# XBee_FX_I2C_Interface_v1_4.net
KiCad netlist of a schematic drawn in EAGLE
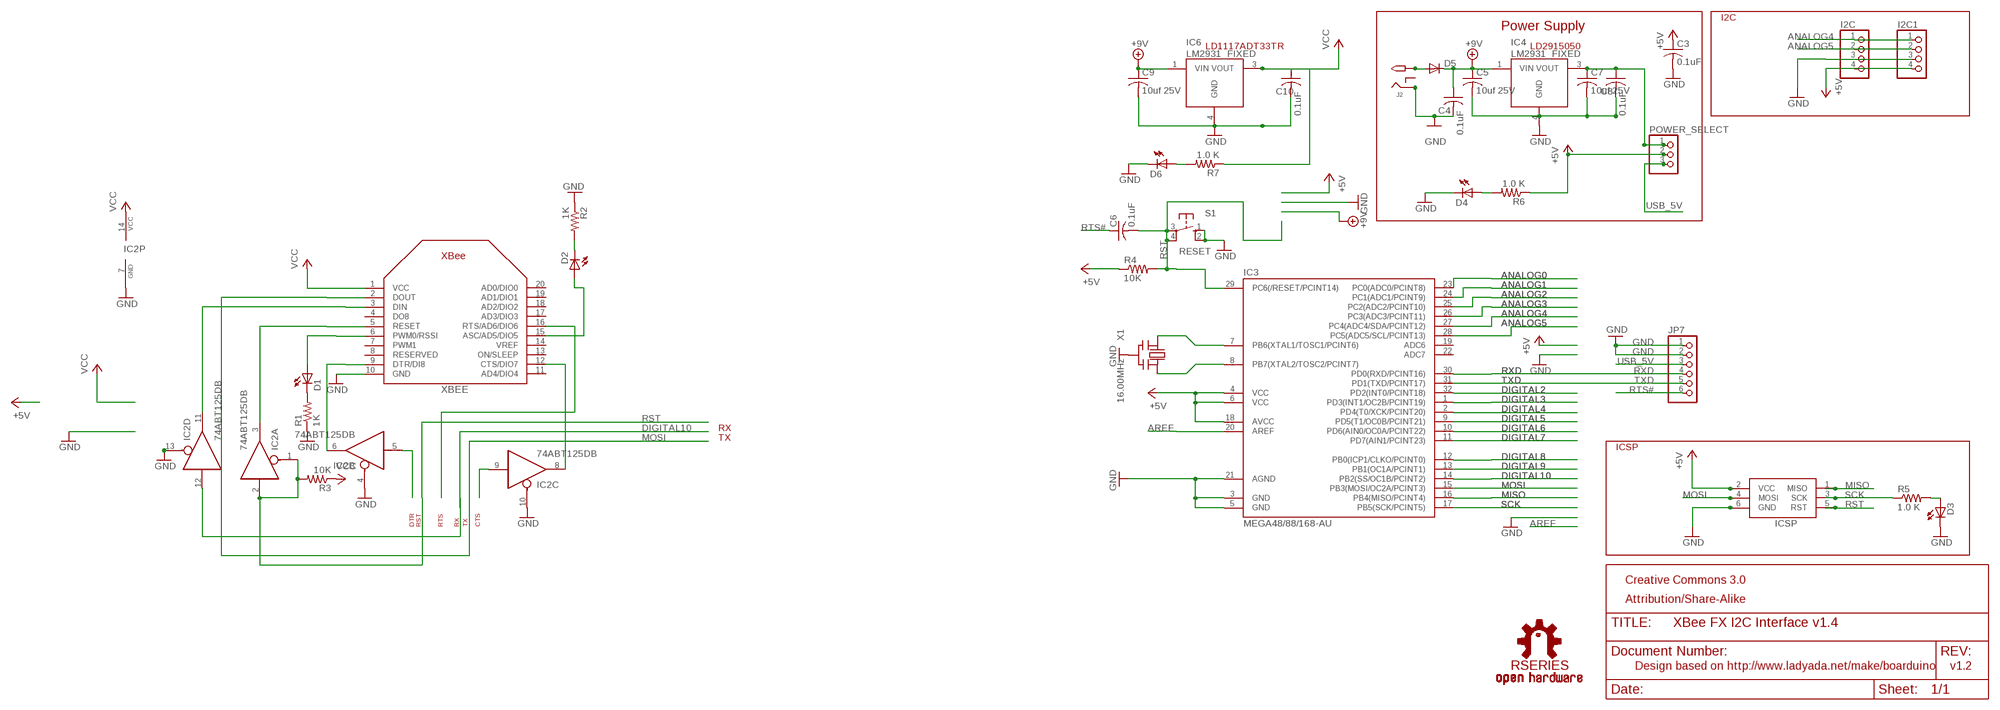
[diagram p0: schematic, sheet 1]

(export (version "E")
  (design (tool "Eeschema 10.0.6"))
  (components
    (comp (ref "C3")
      (value "0.1uF")
      (footprint "eagle-import:C1206K")
      (libsource (lib "eagle-import") (part "C-USC1206K"))
    )
    (comp (ref "C4")
      (value "0.1uF")
      (footprint "eagle-import:C1206K")
      (libsource (lib "eagle-import") (part "C-USC1206K"))
    )
    (comp (ref "C5")
      (value "10uf 25V")
      (footprint "eagle-import:C1206K")
      (libsource (lib "eagle-import") (part "rcl_C-USC1206K"))
    )
    (comp (ref "C6")
      (value "0.1uF")
      (footprint "eagle-import:C1206K")
      (libsource (lib "eagle-import") (part "C-USC1206K"))
    )
    (comp (ref "C7")
      (value "10uf 25V")
      (footprint "eagle-import:C1206K")
      (libsource (lib "eagle-import") (part "rcl_C-USC1206K"))
    )
    (comp (ref "C8")
      (value "0.1uF")
      (footprint "eagle-import:C1206K")
      (libsource (lib "eagle-import") (part "C-USC1206K"))
    )
    (comp (ref "C9")
      (value "10uf 25V")
      (footprint "eagle-import:C1206K")
      (libsource (lib "eagle-import") (part "rcl_C-USC1206K"))
    )
    (comp (ref "C10")
      (value "0.1uF")
      (footprint "eagle-import:C1206K")
      (libsource (lib "eagle-import") (part "C-USC1206K"))
    )
    (comp (ref "D1")
      (value "LEDCHIPLED_1206")
      (footprint "eagle-import:CHIPLED_1206")
      (libsource (lib "eagle-import") (part "LEDCHIPLED_1206"))
    )
    (comp (ref "D2")
      (value "LEDCHIPLED_1206")
      (footprint "eagle-import:CHIPLED_1206")
      (libsource (lib "eagle-import") (part "LEDCHIPLED_1206"))
    )
    (comp (ref "D3")
      (value "RED")
      (footprint "eagle-import:CHIPLED_1206")
      (libsource (lib "eagle-import") (part "LEDCHIPLED_1206"))
    )
    (comp (ref "D4")
      (value "LEDCHIPLED_1206")
      (footprint "eagle-import:CHIPLED_1206")
      (libsource (lib "eagle-import") (part "LEDCHIPLED_1206"))
    )
    (comp (ref "D5")
      (value "DIODE-SMB")
      (footprint "eagle-import:SMB")
      (libsource (lib "eagle-import") (part "DIODE-SMB"))
    )
    (comp (ref "D6")
      (value "LEDCHIPLED_1206")
      (footprint "eagle-import:CHIPLED_1206")
      (libsource (lib "eagle-import") (part "LEDCHIPLED_1206"))
    )
    (comp (ref "I2C")
      (value "PINHD-1X4CB")
      (footprint "eagle-import:1X04-CB")
      (libsource (lib "eagle-import") (part "PINHD-1X4CB"))
    )
    (comp (ref "I2C1")
      (value "PINHD-1X4CB")
      (footprint "eagle-import:1X04-CB")
      (libsource (lib "eagle-import") (part "PINHD-1X4CB"))
    )
    (comp (ref "IC2")
      (value "74ABT125DB")
      (footprint "eagle-import:SSOP14")
      (libsource (lib "eagle-import") (part "74125DBABT"))
    )
    (comp (ref "IC3")
      (value "MEGA48/88/168-AU")
      (footprint "eagle-import:TQFP32-08")
      (libsource (lib "eagle-import") (part "MEGA48/88/168-AU"))
    )
    (comp (ref "IC4")
      (value "LM2931_FIXED")
      (footprint "eagle-import:DPAK")
      (libsource (lib "eagle-import") (part "LM2931_FIXED"))
    )
    (comp (ref "IC6")
      (value "LM2931_FIXED")
      (footprint "eagle-import:DPAK")
      (libsource (lib "eagle-import") (part "LM2931_FIXED"))
    )
    (comp (ref "ICSP")
      (value "AVRISP-6")
      (footprint "eagle-import:AVRISP")
      (libsource (lib "eagle-import") (part "AVRISP-6"))
    )
    (comp (ref "J2")
      (value "2.1MMJACK")
      (footprint "eagle-import:PJ-102A")
      (libsource (lib "eagle-import") (part "2.1MMJACK"))
    )
    (comp (ref "JP7")
      (value "PINHD-1X6CLEAN")
      (footprint "eagle-import:1X06-CLEAN")
      (libsource (lib "eagle-import") (part "PINHD-1X6CLEAN"))
    )
    (comp (ref "POWER_SELECT")
      (value "PINHD-1X3")
      (footprint "eagle-import:1X03")
      (libsource (lib "eagle-import") (part "PINHD-1X3"))
    )
    (comp (ref "R1")
      (value "1K")
      (footprint "eagle-import:R1206")
      (libsource (lib "eagle-import") (part "rcl-ez_R-US_R1206"))
    )
    (comp (ref "R2")
      (value "1K")
      (footprint "eagle-import:R1206")
      (libsource (lib "eagle-import") (part "rcl-ez_R-US_R1206"))
    )
    (comp (ref "R3")
      (value "10K")
      (footprint "eagle-import:R1206")
      (libsource (lib "eagle-import") (part "rcl-ez_R-US_R1206"))
    )
    (comp (ref "R4")
      (value "10K")
      (footprint "eagle-import:R1206")
      (libsource (lib "eagle-import") (part "rcl-ez_R-US_R1206"))
    )
    (comp (ref "R5")
      (value "1.0 K")
      (footprint "eagle-import:M1206")
      (libsource (lib "eagle-import") (part "R-US_M1206"))
    )
    (comp (ref "R6")
      (value "1.0 K")
      (footprint "eagle-import:M1206")
      (libsource (lib "eagle-import") (part "R-US_M1206"))
    )
    (comp (ref "R7")
      (value "1.0 K")
      (footprint "eagle-import:M1206")
      (libsource (lib "eagle-import") (part "R-US_M1206"))
    )
    (comp (ref "S1")
      (value "RESET")
      (footprint "eagle-import:B3F-10XX")
      (libsource (lib "eagle-import") (part "10-XX"))
    )
    (comp (ref "U$6")
      (value "RSERIES-OSHW-LOGOMEDIUM")
      (footprint "eagle-import:RSERIES-OSHW-LOGO-MEDIUM")
      (libsource (lib "eagle-import") (part "RSERIES-OSHW-LOGOMEDIUM"))
    )
    (comp (ref "X1")
      (value "16.00MHz")
      (footprint "eagle-import:CERM_OSC")
      (libsource (lib "eagle-import") (part "CERMOSCILL"))
    )
    (comp (ref "XBEE")
      (value "XBEE")
      (footprint "eagle-import:XBEE")
      (libsource (lib "eagle-import") (part "XBEE"))
    )
  )
  (nets
    (net (code "1") (name "+5V") (class "Default")
      (node (ref "C3") (pin "1") (pinfunction "1_1") (pintype "passive"))
      (node (ref "I2C") (pin "4") (pinfunction "4_4") (pintype "passive"))
      (node (ref "I2C1") (pin "4") (pinfunction "4_4") (pintype "passive"))
      (node (ref "IC3") (pin "18") (pinfunction "AVCC_18") (pintype "passive"))
      (node (ref "IC3") (pin "4") (pinfunction "VCC_4") (pintype "power_in"))
      (node (ref "IC3") (pin "6") (pinfunction "VCC_6") (pintype "power_in"))
      (node (ref "ICSP") (pin "2") (pinfunction "VCC_2") (pintype "power_in"))
      (node (ref "POWER_SELECT") (pin "2") (pinfunction "2_2") (pintype "passive"))
      (node (ref "R4") (pin "1") (pinfunction "1_1") (pintype "passive"))
      (node (ref "R6") (pin "1") (pinfunction "1_1") (pintype "passive"))
    )
    (net (code "2") (name "+9V") (class "Default")
      (node (ref "C4") (pin "1") (pinfunction "1_1") (pintype "passive"))
      (node (ref "C5") (pin "1") (pinfunction "1_1") (pintype "passive"))
      (node (ref "C9") (pin "1") (pinfunction "1_1") (pintype "passive"))
      (node (ref "D5") (pin "C") (pinfunction "C_C") (pintype "passive"))
      (node (ref "IC4") (pin "1") (pinfunction "VIN_1") (pintype "bidirectional"))
      (node (ref "IC6") (pin "1") (pinfunction "VIN_1") (pintype "bidirectional"))
    )
    (net (code "3") (name "/ANALOG0") (class "Default")
      (node (ref "IC3") (pin "23") (pinfunction "PC0(ADC0/PCINT8)_23") (pintype "bidirectional"))
    )
    (net (code "4") (name "/ANALOG1") (class "Default")
      (node (ref "IC3") (pin "24") (pinfunction "PC1(ADC1/PCINT9)_24") (pintype "bidirectional"))
    )
    (net (code "5") (name "/ANALOG2") (class "Default")
      (node (ref "IC3") (pin "25") (pinfunction "PC2(ADC2/PCINT10)_25") (pintype "bidirectional"))
    )
    (net (code "6") (name "/ANALOG3") (class "Default")
      (node (ref "IC3") (pin "26") (pinfunction "PC3(ADC3/PCINT11)_26") (pintype "bidirectional"))
    )
    (net (code "7") (name "/ANALOG4") (class "Default")
      (node (ref "I2C") (pin "1") (pinfunction "1_1") (pintype "passive"))
      (node (ref "I2C1") (pin "1") (pinfunction "1_1") (pintype "passive"))
      (node (ref "IC3") (pin "27") (pinfunction "PC4(ADC4/SDA/PCINT12)_27") (pintype "bidirectional"))
    )
    (net (code "8") (name "/ANALOG5") (class "Default")
      (node (ref "I2C") (pin "2") (pinfunction "2_2") (pintype "passive"))
      (node (ref "I2C1") (pin "2") (pinfunction "2_2") (pintype "passive"))
      (node (ref "IC3") (pin "28") (pinfunction "PC5(ADC5/SCL/PCINT13)_28") (pintype "bidirectional"))
    )
    (net (code "9") (name "/AREF") (class "Default")
      (node (ref "IC3") (pin "20") (pinfunction "AREF_20") (pintype "passive"))
    )
    (net (code "10") (name "/DIGITAL2") (class "Default")
      (node (ref "IC3") (pin "32") (pinfunction "PD2(INT0/PCINT18)_32") (pintype "bidirectional"))
    )
    (net (code "11") (name "/DIGITAL3") (class "Default")
      (node (ref "IC3") (pin "1") (pinfunction "PD3(INT1/OC2B/PCINT19)_1") (pintype "bidirectional"))
    )
    (net (code "12") (name "/DIGITAL4") (class "Default")
      (node (ref "IC3") (pin "2") (pinfunction "PD4(T0/XCK/PCINT20)_2") (pintype "bidirectional"))
    )
    (net (code "13") (name "/DIGITAL5") (class "Default")
      (node (ref "IC3") (pin "9") (pinfunction "PD5(T1/OC0B/PCINT21)_9") (pintype "bidirectional"))
    )
    (net (code "14") (name "/DIGITAL6") (class "Default")
      (node (ref "IC3") (pin "10") (pinfunction "PD6(AIN0/OC0A/PCINT22)_10") (pintype "bidirectional"))
    )
    (net (code "15") (name "/DIGITAL7") (class "Default")
      (node (ref "IC3") (pin "11") (pinfunction "PD7(AIN1/PCINT23)_11") (pintype "bidirectional"))
    )
    (net (code "16") (name "/DIGITAL8") (class "Default")
      (node (ref "IC3") (pin "12") (pinfunction "PB0(ICP1/CLKO/PCINT0)_12") (pintype "bidirectional"))
    )
    (net (code "17") (name "/DIGITAL9") (class "Default")
      (node (ref "IC3") (pin "13") (pinfunction "PB1(OC1A/PCINT1)_13") (pintype "bidirectional"))
    )
    (net (code "18") (name "/DIGITAL10") (class "Default")
      (node (ref "IC2") (pin "12") (pinfunction "I_12") (pintype "input"))
      (node (ref "IC3") (pin "14") (pinfunction "PB2(SS/OC1B/PCINT2)_14") (pintype "bidirectional"))
    )
    (net (code "19") (name "/MISO") (class "Default")
      (node (ref "IC3") (pin "16") (pinfunction "PB4(MISO/PCINT4)_16") (pintype "bidirectional"))
      (node (ref "ICSP") (pin "1") (pinfunction "MISO_1") (pintype "input"))
    )
    (net (code "20") (name "/MOSI") (class "Default")
      (node (ref "IC3") (pin "15") (pinfunction "PB3(MOSI/OC2A/PCINT3)_15") (pintype "bidirectional"))
      (node (ref "ICSP") (pin "4") (pinfunction "MOSI_4") (pintype "output"))
      (node (ref "XBEE") (pin "2") (pinfunction "DOUT_2") (pintype "output"))
    )
    (net (code "21") (name "/RST") (class "Default")
      (node (ref "C6") (pin "2") (pinfunction "2_2") (pintype "passive"))
      (node (ref "IC2") (pin "1") (pinfunction "OE_1") (pintype "input"))
      (node (ref "IC2") (pin "2") (pinfunction "I_2") (pintype "input"))
      (node (ref "IC3") (pin "29") (pinfunction "PC6(/RESET/PCINT14)_29") (pintype "bidirectional"))
      (node (ref "ICSP") (pin "5") (pinfunction "RST_5") (pintype "output"))
      (node (ref "R3") (pin "2") (pinfunction "2_2") (pintype "passive"))
      (node (ref "R4") (pin "2") (pinfunction "2_2") (pintype "passive"))
      (node (ref "S1") (pin "3") (pinfunction "P_3") (pintype "passive"))
      (node (ref "S1") (pin "4") (pinfunction "P1_4") (pintype "passive"))
    )
    (net (code "22") (name "/RTS#") (class "Default")
      (node (ref "C6") (pin "1") (pinfunction "1_1") (pintype "passive"))
      (node (ref "JP7") (pin "6") (pinfunction "6_6") (pintype "passive"))
    )
    (net (code "23") (name "/RXD") (class "Default")
      (node (ref "IC3") (pin "30") (pinfunction "PD0(RXD/PCINT16)_30") (pintype "bidirectional"))
      (node (ref "JP7") (pin "4") (pinfunction "4_4") (pintype "passive"))
    )
    (net (code "24") (name "/SCK") (class "Default")
      (node (ref "IC3") (pin "17") (pinfunction "PB5(SCK/PCINT5)_17") (pintype "bidirectional"))
      (node (ref "ICSP") (pin "3") (pinfunction "SCK_3") (pintype "output"))
      (node (ref "R5") (pin "1") (pinfunction "1_1") (pintype "passive"))
    )
    (net (code "25") (name "/TXD") (class "Default")
      (node (ref "IC3") (pin "31") (pinfunction "PD1(TXD/PCINT17)_31") (pintype "bidirectional"))
      (node (ref "JP7") (pin "5") (pinfunction "5_5") (pintype "passive"))
    )
    (net (code "26") (name "/USB_5V") (class "Default")
      (node (ref "JP7") (pin "3") (pinfunction "3_3") (pintype "passive"))
      (node (ref "POWER_SELECT") (pin "3") (pinfunction "3_3") (pintype "passive"))
    )
    (net (code "27") (name "GND") (class "Default")
      (node (ref "C10") (pin "2") (pinfunction "2_2") (pintype "passive"))
      (node (ref "C3") (pin "2") (pinfunction "2_2") (pintype "passive"))
      (node (ref "C4") (pin "2") (pinfunction "2_2") (pintype "passive"))
      (node (ref "C9") (pin "2") (pinfunction "2_2") (pintype "passive"))
      (node (ref "D3") (pin "C") (pinfunction "C_C") (pintype "passive"))
      (node (ref "D4") (pin "C") (pinfunction "C_C") (pintype "passive"))
      (node (ref "D6") (pin "C") (pinfunction "C_C") (pintype "passive"))
      (node (ref "I2C") (pin "3") (pinfunction "3_3") (pintype "passive"))
      (node (ref "I2C1") (pin "3") (pinfunction "3_3") (pintype "passive"))
      (node (ref "IC2") (pin "10") (pinfunction "OE_10") (pintype "input"))
      (node (ref "IC2") (pin "13") (pinfunction "OE_13") (pintype "input"))
      (node (ref "IC2") (pin "4") (pinfunction "OE_4") (pintype "input"))
      (node (ref "IC2") (pin "7") (pinfunction "GND_7") (pintype "power_in"))
      (node (ref "IC3") (pin "21") (pinfunction "AGND_21") (pintype "power_in"))
      (node (ref "IC3") (pin "3") (pinfunction "GND_3") (pintype "power_in"))
      (node (ref "IC3") (pin "5") (pinfunction "GND_5") (pintype "power_in"))
      (node (ref "IC4") (pin "4") (pinfunction "GND_4") (pintype "bidirectional"))
      (node (ref "IC6") (pin "4") (pinfunction "GND_4") (pintype "bidirectional"))
      (node (ref "ICSP") (pin "6") (pinfunction "GND_6") (pintype "power_in"))
      (node (ref "J2") (pin "RING") (pinfunction "RING_RING") (pintype "bidirectional"))
      (node (ref "JP7") (pin "1") (pinfunction "1_1") (pintype "passive"))
      (node (ref "JP7") (pin "2") (pinfunction "2_2") (pintype "passive"))
      (node (ref "R1") (pin "1") (pinfunction "1_1") (pintype "passive"))
      (node (ref "R2") (pin "1") (pinfunction "1_1") (pintype "passive"))
      (node (ref "S1") (pin "1") (pinfunction "S_1") (pintype "passive"))
      (node (ref "S1") (pin "2") (pinfunction "S1_2") (pintype "passive"))
      (node (ref "X1") (pin "P$2") (pinfunction "GND_P$2") (pintype "bidirectional"))
      (node (ref "XBEE") (pin "10") (pinfunction "GND_10") (pintype "power_in"))
    )
    (net (code "28") (name "Net-(C5-Pad2)") (class "Default")
      (node (ref "C5") (pin "2") (pinfunction "2_2") (pintype "passive"))
      (node (ref "C7") (pin "2") (pinfunction "2_2") (pintype "passive"))
      (node (ref "C8") (pin "2") (pinfunction "2_2") (pintype "passive"))
    )
    (net (code "29") (name "Net-(D1-PadC)") (class "Default")
      (node (ref "D1") (pin "C") (pinfunction "C_C") (pintype "passive"))
      (node (ref "R1") (pin "2") (pinfunction "2_2") (pintype "passive"))
    )
    (net (code "30") (name "Net-(D2-PadC)") (class "Default")
      (node (ref "D2") (pin "C") (pinfunction "C_C") (pintype "passive"))
      (node (ref "R2") (pin "2") (pinfunction "2_2") (pintype "passive"))
    )
    (net (code "31") (name "Net-(D3-PadA)") (class "Default")
      (node (ref "D3") (pin "A") (pinfunction "A_A") (pintype "passive"))
      (node (ref "R5") (pin "2") (pinfunction "2_2") (pintype "passive"))
    )
    (net (code "32") (name "Net-(D4-PadA)") (class "Default")
      (node (ref "D4") (pin "A") (pinfunction "A_A") (pintype "passive"))
      (node (ref "R6") (pin "2") (pinfunction "2_2") (pintype "passive"))
    )
    (net (code "33") (name "Net-(D5-PadA)") (class "Default")
      (node (ref "D5") (pin "A") (pinfunction "A_A") (pintype "passive"))
      (node (ref "J2") (pin "TIP") (pinfunction "TIP_TIP") (pintype "bidirectional"))
    )
    (net (code "34") (name "Net-(D6-PadA)") (class "Default")
      (node (ref "D6") (pin "A") (pinfunction "A_A") (pintype "passive"))
      (node (ref "R7") (pin "2") (pinfunction "2_2") (pintype "passive"))
    )
    (net (code "35") (name "Net-(IC2A-O)") (class "Default")
      (node (ref "IC2") (pin "3") (pinfunction "O_3") (pintype "tri_state"))
      (node (ref "XBEE") (pin "5") (pinfunction "RESET_5") (pintype "input"))
    )
    (net (code "36") (name "Net-(IC2B-O)") (class "Default")
      (node (ref "IC2") (pin "6") (pinfunction "O_6") (pintype "tri_state"))
      (node (ref "XBEE") (pin "9") (pinfunction "DTR/DI8_9") (pintype "input"))
    )
    (net (code "37") (name "Net-(IC2C-O)") (class "Default")
      (node (ref "IC2") (pin "8") (pinfunction "O_8") (pintype "tri_state"))
      (node (ref "XBEE") (pin "12") (pinfunction "CTS/DIO7_12") (pintype "bidirectional"))
    )
    (net (code "38") (name "Net-(IC2D-O)") (class "Default")
      (node (ref "IC2") (pin "11") (pinfunction "O_11") (pintype "tri_state"))
      (node (ref "XBEE") (pin "3") (pinfunction "DIN_3") (pintype "input"))
    )
    (net (code "39") (name "Net-(IC3-PB6(XTAL1{slash}TOSC1{slash}PCINT6))") (class "Default")
      (node (ref "IC3") (pin "7") (pinfunction "PB6(XTAL1/TOSC1/PCINT6)_7") (pintype "bidirectional"))
      (node (ref "X1") (pin "P$1") (pinfunction "IN_P$1") (pintype "bidirectional"))
    )
    (net (code "40") (name "Net-(IC3-PB7(XTAL2{slash}TOSC2{slash}PCINT7))") (class "Default")
      (node (ref "IC3") (pin "8") (pinfunction "PB7(XTAL2/TOSC2/PCINT7)_8") (pintype "bidirectional"))
      (node (ref "X1") (pin "P$3") (pinfunction "OUT_P$3") (pintype "bidirectional"))
    )
    (net (code "41") (name "Net-(IC4-VOUT)") (class "Default")
      (node (ref "C7") (pin "1") (pinfunction "1_1") (pintype "passive"))
      (node (ref "C8") (pin "1") (pinfunction "1_1") (pintype "passive"))
      (node (ref "IC4") (pin "3") (pinfunction "VOUT_3") (pintype "bidirectional"))
      (node (ref "POWER_SELECT") (pin "1") (pinfunction "1_1") (pintype "passive"))
    )
    (net (code "42") (name "Net-(XBEE-ASC{slash}AD5{slash}DIO5)") (class "Default")
      (node (ref "D2") (pin "A") (pinfunction "A_A") (pintype "passive"))
      (node (ref "XBEE") (pin "15") (pinfunction "ASC/AD5/DIO5_15") (pintype "bidirectional"))
    )
    (net (code "43") (name "Net-(XBEE-PWM0{slash}RSSI)") (class "Default")
      (node (ref "D1") (pin "A") (pinfunction "A_A") (pintype "passive"))
      (node (ref "XBEE") (pin "6") (pinfunction "PWM0/RSSI_6") (pintype "output"))
    )
    (net (code "44") (name "VCC") (class "Default")
      (node (ref "C10") (pin "1") (pinfunction "1_1") (pintype "passive"))
      (node (ref "IC2") (pin "14") (pinfunction "VCC_14") (pintype "power_in"))
      (node (ref "IC6") (pin "3") (pinfunction "VOUT_3") (pintype "bidirectional"))
      (node (ref "R3") (pin "1") (pinfunction "1_1") (pintype "passive"))
      (node (ref "R7") (pin "1") (pinfunction "1_1") (pintype "passive"))
      (node (ref "XBEE") (pin "1") (pinfunction "VCC_1") (pintype "power_in"))
    )
    (net (code "45") (name "unconnected-(IC2B-I-Pad5)") (class "Default")
      (node (ref "IC2") (pin "5") (pinfunction "I_5") (pintype "input"))
    )
    (net (code "46") (name "unconnected-(IC2C-I-Pad9)") (class "Default")
      (node (ref "IC2") (pin "9") (pinfunction "I_9") (pintype "input"))
    )
    (net (code "47") (name "unconnected-(IC3-ADC6-Pad19)") (class "Default")
      (node (ref "IC3") (pin "19") (pinfunction "ADC6_19") (pintype "passive"))
    )
    (net (code "48") (name "unconnected-(IC3-ADC7-Pad22)") (class "Default")
      (node (ref "IC3") (pin "22") (pinfunction "ADC7_22") (pintype "passive"))
    )
    (net (code "49") (name "unconnected-(J2-PadRING_SW)") (class "Default")
      (node (ref "J2") (pin "RING_SW") (pinfunction "RING_SW_RING_SW") (pintype "bidirectional"))
    )
    (net (code "50") (name "unconnected-(XBEE-AD0{slash}DIO0-Pad20)") (class "Default")
      (node (ref "XBEE") (pin "20") (pinfunction "AD0/DIO0_20") (pintype "bidirectional"))
    )
    (net (code "51") (name "unconnected-(XBEE-AD1{slash}DIO1-Pad19)") (class "Default")
      (node (ref "XBEE") (pin "19") (pinfunction "AD1/DIO1_19") (pintype "bidirectional"))
    )
    (net (code "52") (name "unconnected-(XBEE-AD2{slash}DIO2-Pad18)") (class "Default")
      (node (ref "XBEE") (pin "18") (pinfunction "AD2/DIO2_18") (pintype "bidirectional"))
    )
    (net (code "53") (name "unconnected-(XBEE-AD3{slash}DIO3-Pad17)") (class "Default")
      (node (ref "XBEE") (pin "17") (pinfunction "AD3/DIO3_17") (pintype "bidirectional"))
    )
    (net (code "54") (name "unconnected-(XBEE-AD4{slash}DIO4-Pad11)") (class "Default")
      (node (ref "XBEE") (pin "11") (pinfunction "AD4/DIO4_11") (pintype "bidirectional"))
    )
    (net (code "55") (name "unconnected-(XBEE-DO8-Pad4)") (class "Default")
      (node (ref "XBEE") (pin "4") (pinfunction "DO8_4") (pintype "output"))
    )
    (net (code "56") (name "unconnected-(XBEE-ON{slash}SLEEP-Pad13)") (class "Default")
      (node (ref "XBEE") (pin "13") (pinfunction "ON/SLEEP_13") (pintype "output"))
    )
    (net (code "57") (name "unconnected-(XBEE-PWM1-Pad7)") (class "Default")
      (node (ref "XBEE") (pin "7") (pinfunction "PWM1_7") (pintype "output"))
    )
    (net (code "58") (name "unconnected-(XBEE-RESERVED-Pad8)") (class "Default")
      (node (ref "XBEE") (pin "8") (pinfunction "RESERVED_8") (pintype "no_connect"))
    )
    (net (code "59") (name "unconnected-(XBEE-RTS{slash}AD6{slash}DIO6-Pad16)") (class "Default")
      (node (ref "XBEE") (pin "16") (pinfunction "RTS/AD6/DIO6_16") (pintype "bidirectional"))
    )
    (net (code "60") (name "unconnected-(XBEE-VREF-Pad14)") (class "Default")
      (node (ref "XBEE") (pin "14") (pinfunction "VREF_14") (pintype "input"))
    )
  )
)
